# relay_dip_v01.net
KiCad netlist of a schematic drawn in EAGLE
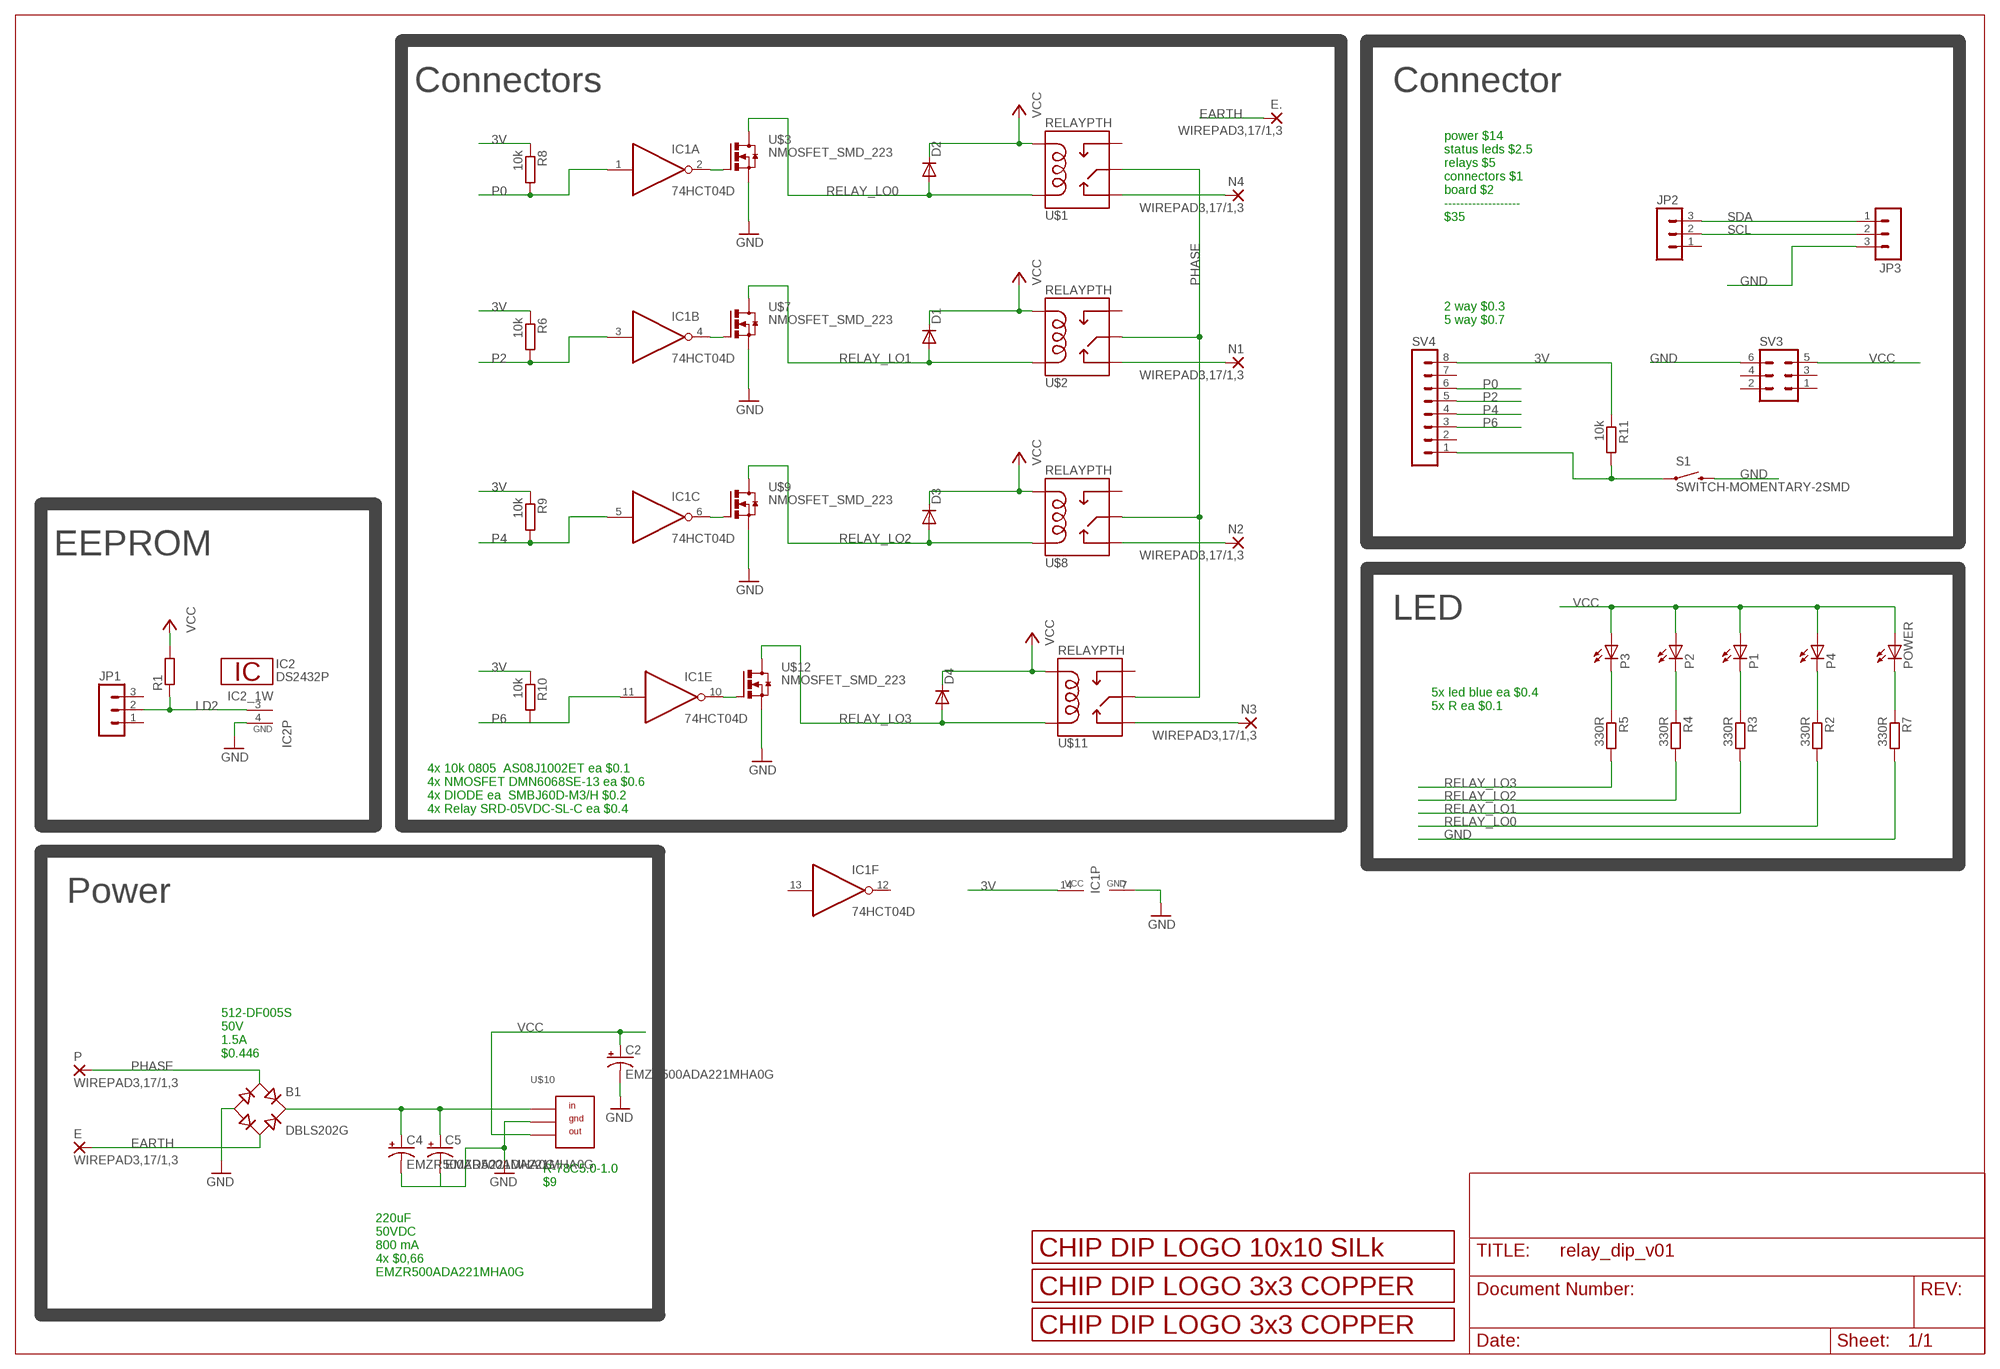
[diagram p0: schematic, sheet 1]

(export (version "E")
  (design (tool "Eeschema 10.0.6"))
  (components
    (comp (ref "B1")
      (value "DBLS202G")
      (footprint "eagle-import:DBS")
      (libsource (lib "eagle-import") (part "DB?GLS202"))
    )
    (comp (ref "C2")
      (value "EMZR500ADA221MHA0G")
      (footprint "eagle-import:150CLZ-0810")
      (libsource (lib "eagle-import") (part "CPOL-US150CLZ-0810"))
    )
    (comp (ref "C4")
      (value "EMZR500ADA221MHA0G")
      (footprint "eagle-import:150CLZ-0810")
      (libsource (lib "eagle-import") (part "CPOL-US150CLZ-0810"))
    )
    (comp (ref "C5")
      (value "EMZR500ADA221MHA0G")
      (footprint "eagle-import:150CLZ-0810")
      (libsource (lib "eagle-import") (part "CPOL-US150CLZ-0810"))
    )
    (comp (ref "D1")
      (value "DIODE-SMB")
      (footprint "eagle-import:SMB")
      (libsource (lib "eagle-import") (part "DIODE-SMB"))
    )
    (comp (ref "D2")
      (value "DIODE-SMB")
      (footprint "eagle-import:SMB")
      (libsource (lib "eagle-import") (part "DIODE-SMB"))
    )
    (comp (ref "D3")
      (value "DIODE-SMB")
      (footprint "eagle-import:SMB")
      (libsource (lib "eagle-import") (part "DIODE-SMB"))
    )
    (comp (ref "D4")
      (value "DIODE-SMB")
      (footprint "eagle-import:SMB")
      (libsource (lib "eagle-import") (part "DIODE-SMB"))
    )
    (comp (ref "E")
      (value "WIREPAD3,17/1,3")
      (footprint "eagle-import:3,17_1,3")
      (libsource (lib "eagle-import") (part "WIREPAD3,17/1,3"))
    )
    (comp (ref "E.")
      (value "WIREPAD3,17/1,3")
      (footprint "eagle-import:3,17_1,3")
      (libsource (lib "eagle-import") (part "WIREPAD3,17/1,3"))
    )
    (comp (ref "IC1")
      (value "74HCT04D")
      (footprint "eagle-import:SO14")
      (libsource (lib "eagle-import") (part "7404DHCT"))
    )
    (comp (ref "IC2")
      (value "DS2432P")
      (footprint "eagle-import:TSOC6")
      (libsource (lib "eagle-import") (part "DS2432P"))
    )
    (comp (ref "JP1")
      (value "MA03-1")
      (footprint "eagle-import:MA03-1")
      (libsource (lib "eagle-import") (part "MA03-1"))
    )
    (comp (ref "JP2")
      (value "MA03-1")
      (footprint "eagle-import:MA03-1")
      (libsource (lib "eagle-import") (part "MA03-1"))
    )
    (comp (ref "JP3")
      (value "MA03-1")
      (footprint "eagle-import:MA03-1")
      (libsource (lib "eagle-import") (part "MA03-1"))
    )
    (comp (ref "N1")
      (value "WIREPAD3,17/1,3")
      (footprint "eagle-import:3,17_1,3")
      (libsource (lib "eagle-import") (part "WIREPAD3,17/1,3"))
    )
    (comp (ref "N2")
      (value "WIREPAD3,17/1,3")
      (footprint "eagle-import:3,17_1,3")
      (libsource (lib "eagle-import") (part "WIREPAD3,17/1,3"))
    )
    (comp (ref "N3")
      (value "WIREPAD3,17/1,3")
      (footprint "eagle-import:3,17_1,3")
      (libsource (lib "eagle-import") (part "WIREPAD3,17/1,3"))
    )
    (comp (ref "N4")
      (value "WIREPAD3,17/1,3")
      (footprint "eagle-import:3,17_1,3")
      (libsource (lib "eagle-import") (part "WIREPAD3,17/1,3"))
    )
    (comp (ref "P")
      (value "WIREPAD3,17/1,3")
      (footprint "eagle-import:3,17_1,3")
      (libsource (lib "eagle-import") (part "WIREPAD3,17/1,3"))
    )
    (comp (ref "P1")
      (value "LEDCHIP-LED0805")
      (footprint "eagle-import:CHIP-LED0805")
      (libsource (lib "eagle-import") (part "LEDCHIP-LED0805"))
    )
    (comp (ref "P2")
      (value "LEDCHIP-LED0805")
      (footprint "eagle-import:CHIP-LED0805")
      (libsource (lib "eagle-import") (part "LEDCHIP-LED0805"))
    )
    (comp (ref "P3")
      (value "LEDCHIP-LED0805")
      (footprint "eagle-import:CHIP-LED0805")
      (libsource (lib "eagle-import") (part "LEDCHIP-LED0805"))
    )
    (comp (ref "P4")
      (value "LEDCHIP-LED0805")
      (footprint "eagle-import:CHIP-LED0805")
      (libsource (lib "eagle-import") (part "LEDCHIP-LED0805"))
    )
    (comp (ref "POWER")
      (value "LEDCHIP-LED0805")
      (footprint "eagle-import:CHIP-LED0805")
      (libsource (lib "eagle-import") (part "LEDCHIP-LED0805"))
    )
    (comp (ref "R1")
      (value "R-EU_R0805")
      (footprint "eagle-import:R0805")
      (libsource (lib "eagle-import") (part "R-EU_R0805"))
    )
    (comp (ref "R2")
      (value "330R")
      (footprint "eagle-import:R0805")
      (libsource (lib "eagle-import") (part "R-EU_R0805"))
    )
    (comp (ref "R3")
      (value "330R")
      (footprint "eagle-import:R0805")
      (libsource (lib "eagle-import") (part "R-EU_R0805"))
    )
    (comp (ref "R4")
      (value "330R")
      (footprint "eagle-import:R0805")
      (libsource (lib "eagle-import") (part "R-EU_R0805"))
    )
    (comp (ref "R5")
      (value "330R")
      (footprint "eagle-import:R0805")
      (libsource (lib "eagle-import") (part "R-EU_R0805"))
    )
    (comp (ref "R6")
      (value "10k")
      (footprint "eagle-import:R0805")
      (libsource (lib "eagle-import") (part "R-EU_R0805"))
    )
    (comp (ref "R7")
      (value "330R")
      (footprint "eagle-import:R0805")
      (libsource (lib "eagle-import") (part "R-EU_R0805"))
    )
    (comp (ref "R8")
      (value "10k")
      (footprint "eagle-import:R0805")
      (libsource (lib "eagle-import") (part "R-EU_R0805"))
    )
    (comp (ref "R9")
      (value "10k")
      (footprint "eagle-import:R0805")
      (libsource (lib "eagle-import") (part "R-EU_R0805"))
    )
    (comp (ref "R10")
      (value "10k")
      (footprint "eagle-import:R0805")
      (libsource (lib "eagle-import") (part "R-EU_R0805"))
    )
    (comp (ref "R11")
      (value "10k")
      (footprint "eagle-import:R0805")
      (libsource (lib "eagle-import") (part "R-EU_R0805"))
    )
    (comp (ref "S1")
      (value "SWITCH-MOMENTARY-2SMD")
      (footprint "eagle-import:TACTILE-SWITCH-SMD")
      (libsource (lib "eagle-import") (part "SWITCH-MOMENTARY-2SMD"))
    )
    (comp (ref "SV3")
      (value "MA03-2")
      (footprint "eagle-import:MA03-2")
      (libsource (lib "eagle-import") (part "MA03-2"))
    )
    (comp (ref "SV4")
      (value "MA08-1")
      (footprint "eagle-import:MA08-1")
      (libsource (lib "eagle-import") (part "MA08-1"))
    )
    (comp (ref "U$1")
      (value "RELAYPTH")
      (footprint "eagle-import:SRD-05VDC-SL-C")
      (libsource (lib "eagle-import") (part "RELAYPTH"))
    )
    (comp (ref "U$2")
      (value "RELAYPTH")
      (footprint "eagle-import:SRD-05VDC-SL-C")
      (libsource (lib "eagle-import") (part "RELAYPTH"))
    )
    (comp (ref "U$3")
      (value "NMOSFET_SMD_223")
      (footprint "eagle-import:SOT223")
      (libsource (lib "eagle-import") (part "NMOSFET_SMD_223"))
    )
    (comp (ref "U$4")
      (value "LOGO_3X3_COPPER")
      (footprint "eagle-import:LOGO_3X3_COPPER")
      (libsource (lib "eagle-import") (part "LOGO_3X3_COPPER"))
    )
    (comp (ref "U$5")
      (value "LOGO_10X10_SILK")
      (footprint "eagle-import:LOGO_10X10_SILK")
      (libsource (lib "eagle-import") (part "LOGO_10X10_SILK"))
    )
    (comp (ref "U$6")
      (value "LOGO_3X3_COPPER")
      (footprint "eagle-import:LOGO_3X3_COPPER")
      (libsource (lib "eagle-import") (part "LOGO_3X3_COPPER"))
    )
    (comp (ref "U$7")
      (value "NMOSFET_SMD_223")
      (footprint "eagle-import:SOT223")
      (libsource (lib "eagle-import") (part "NMOSFET_SMD_223"))
    )
    (comp (ref "U$8")
      (value "RELAYPTH")
      (footprint "eagle-import:SRD-05VDC-SL-C")
      (libsource (lib "eagle-import") (part "RELAYPTH"))
    )
    (comp (ref "U$9")
      (value "NMOSFET_SMD_223")
      (footprint "eagle-import:SOT223")
      (libsource (lib "eagle-import") (part "NMOSFET_SMD_223"))
    )
    (comp (ref "U$10")
      (value "R-7805-1.0")
      (footprint "eagle-import:SIP3")
      (libsource (lib "eagle-import") (part "R-7805-1.0"))
    )
    (comp (ref "U$11")
      (value "RELAYPTH")
      (footprint "eagle-import:SRD-05VDC-SL-C")
      (libsource (lib "eagle-import") (part "RELAYPTH"))
    )
    (comp (ref "U$12")
      (value "NMOSFET_SMD_223")
      (footprint "eagle-import:SOT223")
      (libsource (lib "eagle-import") (part "NMOSFET_SMD_223"))
    )
  )
  (nets
    (net (code "1") (name "/3V") (class "Default")
      (node (ref "IC1") (pin "14") (pinfunction "VCC_14") (pintype "power_in"))
      (node (ref "R10") (pin "1") (pinfunction "1_1") (pintype "passive"))
      (node (ref "R11") (pin "1") (pinfunction "1_1") (pintype "passive"))
      (node (ref "R6") (pin "1") (pinfunction "1_1") (pintype "passive"))
      (node (ref "R8") (pin "1") (pinfunction "1_1") (pintype "passive"))
      (node (ref "R9") (pin "1") (pinfunction "1_1") (pintype "passive"))
      (node (ref "SV4") (pin "8") (pinfunction "8_8") (pintype "passive"))
    )
    (net (code "2") (name "/EARTH") (class "Default")
      (node (ref "B1") (pin "AC2") (pinfunction "AC2_AC2") (pintype "passive"))
      (node (ref "E") (pin "1") (pinfunction "P_1") (pintype "passive"))
      (node (ref "E.") (pin "1") (pinfunction "P_1") (pintype "passive"))
    )
    (net (code "3") (name "/LD2") (class "Default")
      (node (ref "IC2") (pin "3") (pinfunction "1W_3") (pintype "power_in"))
      (node (ref "JP1") (pin "2") (pinfunction "2_2") (pintype "passive"))
      (node (ref "R1") (pin "1") (pinfunction "1_1") (pintype "passive"))
    )
    (net (code "4") (name "/P0") (class "Default")
      (node (ref "IC1") (pin "1") (pinfunction "I_1") (pintype "input"))
      (node (ref "R8") (pin "2") (pinfunction "2_2") (pintype "passive"))
      (node (ref "SV4") (pin "6") (pinfunction "6_6") (pintype "passive"))
    )
    (net (code "5") (name "/P2") (class "Default")
      (node (ref "IC1") (pin "3") (pinfunction "I_3") (pintype "input"))
      (node (ref "R6") (pin "2") (pinfunction "2_2") (pintype "passive"))
      (node (ref "SV4") (pin "5") (pinfunction "5_5") (pintype "passive"))
    )
    (net (code "6") (name "/P4") (class "Default")
      (node (ref "IC1") (pin "5") (pinfunction "I_5") (pintype "input"))
      (node (ref "R9") (pin "2") (pinfunction "2_2") (pintype "passive"))
      (node (ref "SV4") (pin "4") (pinfunction "4_4") (pintype "passive"))
    )
    (net (code "7") (name "/P6") (class "Default")
      (node (ref "IC1") (pin "11") (pinfunction "I_11") (pintype "input"))
      (node (ref "R10") (pin "2") (pinfunction "2_2") (pintype "passive"))
      (node (ref "SV4") (pin "3") (pinfunction "3_3") (pintype "passive"))
    )
    (net (code "8") (name "/PHASE") (class "Default")
      (node (ref "B1") (pin "AC1") (pinfunction "AC1_AC1") (pintype "passive"))
      (node (ref "P") (pin "1") (pinfunction "P_1") (pintype "passive"))
      (node (ref "U$1") (pin "SWCOMMON") (pinfunction "SWCOMMON_SWCOMMON") (pintype "bidirectional"))
      (node (ref "U$11") (pin "SWCOMMON") (pinfunction "SWCOMMON_SWCOMMON") (pintype "bidirectional"))
      (node (ref "U$2") (pin "SWCOMMON") (pinfunction "SWCOMMON_SWCOMMON") (pintype "bidirectional"))
      (node (ref "U$8") (pin "SWCOMMON") (pinfunction "SWCOMMON_SWCOMMON") (pintype "bidirectional"))
    )
    (net (code "9") (name "/RELAY_LO0") (class "Default")
      (node (ref "D2") (pin "A") (pinfunction "A_A") (pintype "passive"))
      (node (ref "R2") (pin "2") (pinfunction "2_2") (pintype "passive"))
      (node (ref "U$1") (pin "COIL1") (pinfunction "COIL1_COIL1") (pintype "bidirectional"))
      (node (ref "U$3") (pin "2") (pinfunction "D_2") (pintype "passive"))
      (node (ref "U$3") (pin "4") (pinfunction "D_4") (pintype "passive"))
    )
    (net (code "10") (name "/RELAY_LO1") (class "Default")
      (node (ref "D1") (pin "A") (pinfunction "A_A") (pintype "passive"))
      (node (ref "R3") (pin "2") (pinfunction "2_2") (pintype "passive"))
      (node (ref "U$2") (pin "COIL1") (pinfunction "COIL1_COIL1") (pintype "bidirectional"))
      (node (ref "U$7") (pin "2") (pinfunction "D_2") (pintype "passive"))
      (node (ref "U$7") (pin "4") (pinfunction "D_4") (pintype "passive"))
    )
    (net (code "11") (name "/RELAY_LO2") (class "Default")
      (node (ref "D3") (pin "A") (pinfunction "A_A") (pintype "passive"))
      (node (ref "R4") (pin "2") (pinfunction "2_2") (pintype "passive"))
      (node (ref "U$8") (pin "COIL1") (pinfunction "COIL1_COIL1") (pintype "bidirectional"))
      (node (ref "U$9") (pin "2") (pinfunction "D_2") (pintype "passive"))
      (node (ref "U$9") (pin "4") (pinfunction "D_4") (pintype "passive"))
    )
    (net (code "12") (name "/RELAY_LO3") (class "Default")
      (node (ref "D4") (pin "A") (pinfunction "A_A") (pintype "passive"))
      (node (ref "R5") (pin "2") (pinfunction "2_2") (pintype "passive"))
      (node (ref "U$11") (pin "COIL1") (pinfunction "COIL1_COIL1") (pintype "bidirectional"))
      (node (ref "U$12") (pin "2") (pinfunction "D_2") (pintype "passive"))
      (node (ref "U$12") (pin "4") (pinfunction "D_4") (pintype "passive"))
    )
    (net (code "13") (name "/SCL") (class "Default")
      (node (ref "JP2") (pin "2") (pinfunction "2_2") (pintype "passive"))
      (node (ref "JP3") (pin "2") (pinfunction "2_2") (pintype "passive"))
    )
    (net (code "14") (name "/SDA") (class "Default")
      (node (ref "JP2") (pin "3") (pinfunction "3_3") (pintype "passive"))
      (node (ref "JP3") (pin "1") (pinfunction "1_1") (pintype "passive"))
    )
    (net (code "15") (name "GND") (class "Default")
      (node (ref "B1") (pin "-") (pinfunction "-_-") (pintype "passive"))
      (node (ref "C2") (pin "-") (pinfunction "-_-") (pintype "passive"))
      (node (ref "C4") (pin "-") (pinfunction "-_-") (pintype "passive"))
      (node (ref "C5") (pin "-") (pinfunction "-_-") (pintype "passive"))
      (node (ref "IC1") (pin "7") (pinfunction "GND_7") (pintype "power_in"))
      (node (ref "IC2") (pin "4") (pinfunction "GND_4") (pintype "power_in"))
      (node (ref "JP3") (pin "3") (pinfunction "3_3") (pintype "passive"))
      (node (ref "R7") (pin "2") (pinfunction "2_2") (pintype "passive"))
      (node (ref "S1") (pin "3") (pinfunction "2_3") (pintype "passive"))
      (node (ref "SV3") (pin "6") (pinfunction "6_6") (pintype "passive"))
      (node (ref "U$10") (pin "GND") (pinfunction "GND_GND") (pintype "bidirectional"))
      (node (ref "U$12") (pin "3") (pinfunction "S_3") (pintype "passive"))
      (node (ref "U$3") (pin "3") (pinfunction "S_3") (pintype "passive"))
      (node (ref "U$7") (pin "3") (pinfunction "S_3") (pintype "passive"))
      (node (ref "U$9") (pin "3") (pinfunction "S_3") (pintype "passive"))
    )
    (net (code "16") (name "Net-(B1-Pad+)") (class "Default")
      (node (ref "B1") (pin "+") (pinfunction "+_+") (pintype "passive"))
      (node (ref "C4") (pin "+") (pinfunction "+_+") (pintype "passive"))
      (node (ref "C5") (pin "+") (pinfunction "+_+") (pintype "passive"))
      (node (ref "U$10") (pin "IN") (pinfunction "IN_IN") (pintype "bidirectional"))
    )
    (net (code "17") (name "Net-(IC1A-O)") (class "Default")
      (node (ref "IC1") (pin "2") (pinfunction "O_2") (pintype "output"))
      (node (ref "U$3") (pin "1") (pinfunction "G_1") (pintype "passive"))
    )
    (net (code "18") (name "Net-(IC1B-O)") (class "Default")
      (node (ref "IC1") (pin "4") (pinfunction "O_4") (pintype "output"))
      (node (ref "U$7") (pin "1") (pinfunction "G_1") (pintype "passive"))
    )
    (net (code "19") (name "Net-(IC1C-O)") (class "Default")
      (node (ref "IC1") (pin "6") (pinfunction "O_6") (pintype "output"))
      (node (ref "U$9") (pin "1") (pinfunction "G_1") (pintype "passive"))
    )
    (net (code "20") (name "Net-(IC1E-O)") (class "Default")
      (node (ref "IC1") (pin "10") (pinfunction "O_10") (pintype "output"))
      (node (ref "U$12") (pin "1") (pinfunction "G_1") (pintype "passive"))
    )
    (net (code "21") (name "Net-(N1-P)") (class "Default")
      (node (ref "N1") (pin "1") (pinfunction "P_1") (pintype "passive"))
      (node (ref "U$2") (pin "SWCLOSED") (pinfunction "SWCLOSE_SWCLOSED") (pintype "bidirectional"))
    )
    (net (code "22") (name "Net-(N2-P)") (class "Default")
      (node (ref "N2") (pin "1") (pinfunction "P_1") (pintype "passive"))
      (node (ref "U$8") (pin "SWCLOSED") (pinfunction "SWCLOSE_SWCLOSED") (pintype "bidirectional"))
    )
    (net (code "23") (name "Net-(N3-P)") (class "Default")
      (node (ref "N3") (pin "1") (pinfunction "P_1") (pintype "passive"))
      (node (ref "U$11") (pin "SWCLOSED") (pinfunction "SWCLOSE_SWCLOSED") (pintype "bidirectional"))
    )
    (net (code "24") (name "Net-(N4-P)") (class "Default")
      (node (ref "N4") (pin "1") (pinfunction "P_1") (pintype "passive"))
      (node (ref "U$1") (pin "SWCLOSED") (pinfunction "SWCLOSE_SWCLOSED") (pintype "bidirectional"))
    )
    (net (code "25") (name "Net-(P1-PadC)") (class "Default")
      (node (ref "P1") (pin "C") (pinfunction "C_C") (pintype "passive"))
      (node (ref "R3") (pin "1") (pinfunction "1_1") (pintype "passive"))
    )
    (net (code "26") (name "Net-(P2-PadC)") (class "Default")
      (node (ref "P2") (pin "C") (pinfunction "C_C") (pintype "passive"))
      (node (ref "R4") (pin "1") (pinfunction "1_1") (pintype "passive"))
    )
    (net (code "27") (name "Net-(P3-PadC)") (class "Default")
      (node (ref "P3") (pin "C") (pinfunction "C_C") (pintype "passive"))
      (node (ref "R5") (pin "1") (pinfunction "1_1") (pintype "passive"))
    )
    (net (code "28") (name "Net-(P4-PadC)") (class "Default")
      (node (ref "P4") (pin "C") (pinfunction "C_C") (pintype "passive"))
      (node (ref "R2") (pin "1") (pinfunction "1_1") (pintype "passive"))
    )
    (net (code "29") (name "Net-(POWER-PadC)") (class "Default")
      (node (ref "POWER") (pin "C") (pinfunction "C_C") (pintype "passive"))
      (node (ref "R7") (pin "1") (pinfunction "1_1") (pintype "passive"))
    )
    (net (code "30") (name "Net-(R11-Pad2)") (class "Default")
      (node (ref "R11") (pin "2") (pinfunction "2_2") (pintype "passive"))
      (node (ref "S1") (pin "1") (pinfunction "1_1") (pintype "passive"))
      (node (ref "SV4") (pin "1") (pinfunction "1_1") (pintype "passive"))
    )
    (net (code "31") (name "VCC") (class "Default")
      (node (ref "C2") (pin "+") (pinfunction "+_+") (pintype "passive"))
      (node (ref "D1") (pin "C") (pinfunction "C_C") (pintype "passive"))
      (node (ref "D2") (pin "C") (pinfunction "C_C") (pintype "passive"))
      (node (ref "D3") (pin "C") (pinfunction "C_C") (pintype "passive"))
      (node (ref "D4") (pin "C") (pinfunction "C_C") (pintype "passive"))
      (node (ref "P1") (pin "A") (pinfunction "A_A") (pintype "passive"))
      (node (ref "P2") (pin "A") (pinfunction "A_A") (pintype "passive"))
      (node (ref "P3") (pin "A") (pinfunction "A_A") (pintype "passive"))
      (node (ref "P4") (pin "A") (pinfunction "A_A") (pintype "passive"))
      (node (ref "POWER") (pin "A") (pinfunction "A_A") (pintype "passive"))
      (node (ref "R1") (pin "2") (pinfunction "2_2") (pintype "passive"))
      (node (ref "SV3") (pin "5") (pinfunction "5_5") (pintype "passive"))
      (node (ref "U$1") (pin "COIL0") (pinfunction "COIL0_COIL0") (pintype "bidirectional"))
      (node (ref "U$10") (pin "OUT") (pinfunction "OUT_OUT") (pintype "bidirectional"))
      (node (ref "U$11") (pin "COIL0") (pinfunction "COIL0_COIL0") (pintype "bidirectional"))
      (node (ref "U$2") (pin "COIL0") (pinfunction "COIL0_COIL0") (pintype "bidirectional"))
      (node (ref "U$8") (pin "COIL0") (pinfunction "COIL0_COIL0") (pintype "bidirectional"))
    )
    (net (code "32") (name "unconnected-(IC1F-I-Pad13)") (class "Default")
      (node (ref "IC1") (pin "13") (pinfunction "I_13") (pintype "input"))
    )
    (net (code "33") (name "unconnected-(IC1F-O-Pad12)") (class "Default")
      (node (ref "IC1") (pin "12") (pinfunction "O_12") (pintype "output"))
    )
    (net (code "34") (name "unconnected-(JP1-Pad1)") (class "Default")
      (node (ref "JP1") (pin "1") (pinfunction "1_1") (pintype "passive"))
    )
    (net (code "35") (name "unconnected-(JP1-Pad3)") (class "Default")
      (node (ref "JP1") (pin "3") (pinfunction "3_3") (pintype "passive"))
    )
    (net (code "36") (name "unconnected-(JP2-Pad1)") (class "Default")
      (node (ref "JP2") (pin "1") (pinfunction "1_1") (pintype "passive"))
    )
    (net (code "37") (name "unconnected-(SV3-Pad1)") (class "Default")
      (node (ref "SV3") (pin "1") (pinfunction "1_1") (pintype "passive"))
    )
    (net (code "38") (name "unconnected-(SV3-Pad2)") (class "Default")
      (node (ref "SV3") (pin "2") (pinfunction "2_2") (pintype "passive"))
    )
    (net (code "39") (name "unconnected-(SV3-Pad3)") (class "Default")
      (node (ref "SV3") (pin "3") (pinfunction "3_3") (pintype "passive"))
    )
    (net (code "40") (name "unconnected-(SV3-Pad4)") (class "Default")
      (node (ref "SV3") (pin "4") (pinfunction "4_4") (pintype "passive"))
    )
    (net (code "41") (name "unconnected-(SV4-Pad2)") (class "Default")
      (node (ref "SV4") (pin "2") (pinfunction "2_2") (pintype "passive"))
    )
    (net (code "42") (name "unconnected-(SV4-Pad7)") (class "Default")
      (node (ref "SV4") (pin "7") (pinfunction "7_7") (pintype "passive"))
    )
    (net (code "43") (name "unconnected-(U$1-PadSWOPEN)") (class "Default")
      (node (ref "U$1") (pin "SWOPEN") (pinfunction "SWOPEN_SWOPEN") (pintype "bidirectional"))
    )
    (net (code "44") (name "unconnected-(U$2-PadSWOPEN)") (class "Default")
      (node (ref "U$2") (pin "SWOPEN") (pinfunction "SWOPEN_SWOPEN") (pintype "bidirectional"))
    )
    (net (code "45") (name "unconnected-(U$8-PadSWOPEN)") (class "Default")
      (node (ref "U$8") (pin "SWOPEN") (pinfunction "SWOPEN_SWOPEN") (pintype "bidirectional"))
    )
    (net (code "46") (name "unconnected-(U$11-PadSWOPEN)") (class "Default")
      (node (ref "U$11") (pin "SWOPEN") (pinfunction "SWOPEN_SWOPEN") (pintype "bidirectional"))
    )
  )
)
